# testboard.net
KiCad netlist of a schematic drawn in EAGLE
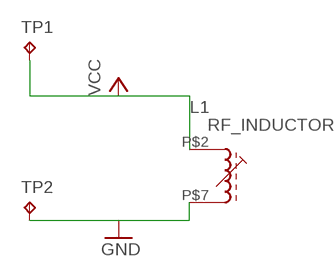
[diagram p0: schematic, sheet 1]

(export (version "E")
  (design (tool "Eeschema 10.0.6"))
  (components
    (comp (ref "L1")
      (value "RF_INDUCTOR")
      (footprint "eagle-import:ADJ_IND_NON_STD_PKG")
      (libsource (lib "eagle-import") (part "RF_INDUCTOR"))
    )
    (comp (ref "TP1")
      (value "TPB2,54")
      (footprint "eagle-import:B2,54")
      (libsource (lib "eagle-import") (part "TPB2,54"))
    )
    (comp (ref "TP2")
      (value "TPB2,54")
      (footprint "eagle-import:B2,54")
      (libsource (lib "eagle-import") (part "TPB2,54"))
    )
  )
  (nets
    (net (code "1") (name "GND") (class "Default")
      (node (ref "L1") (pin "P$7") (pinfunction "E1_P$7") (pintype "passive"))
      (node (ref "TP2") (pin "TP") (pinfunction "TP_TP") (pintype "input"))
    )
    (net (code "2") (name "VCC") (class "Default")
      (node (ref "L1") (pin "P$2") (pinfunction "A1_P$2") (pintype "passive"))
      (node (ref "TP1") (pin "TP") (pinfunction "TP_TP") (pintype "input"))
    )
  )
)
